# demeter.net
KiCad netlist of a schematic drawn in EAGLE
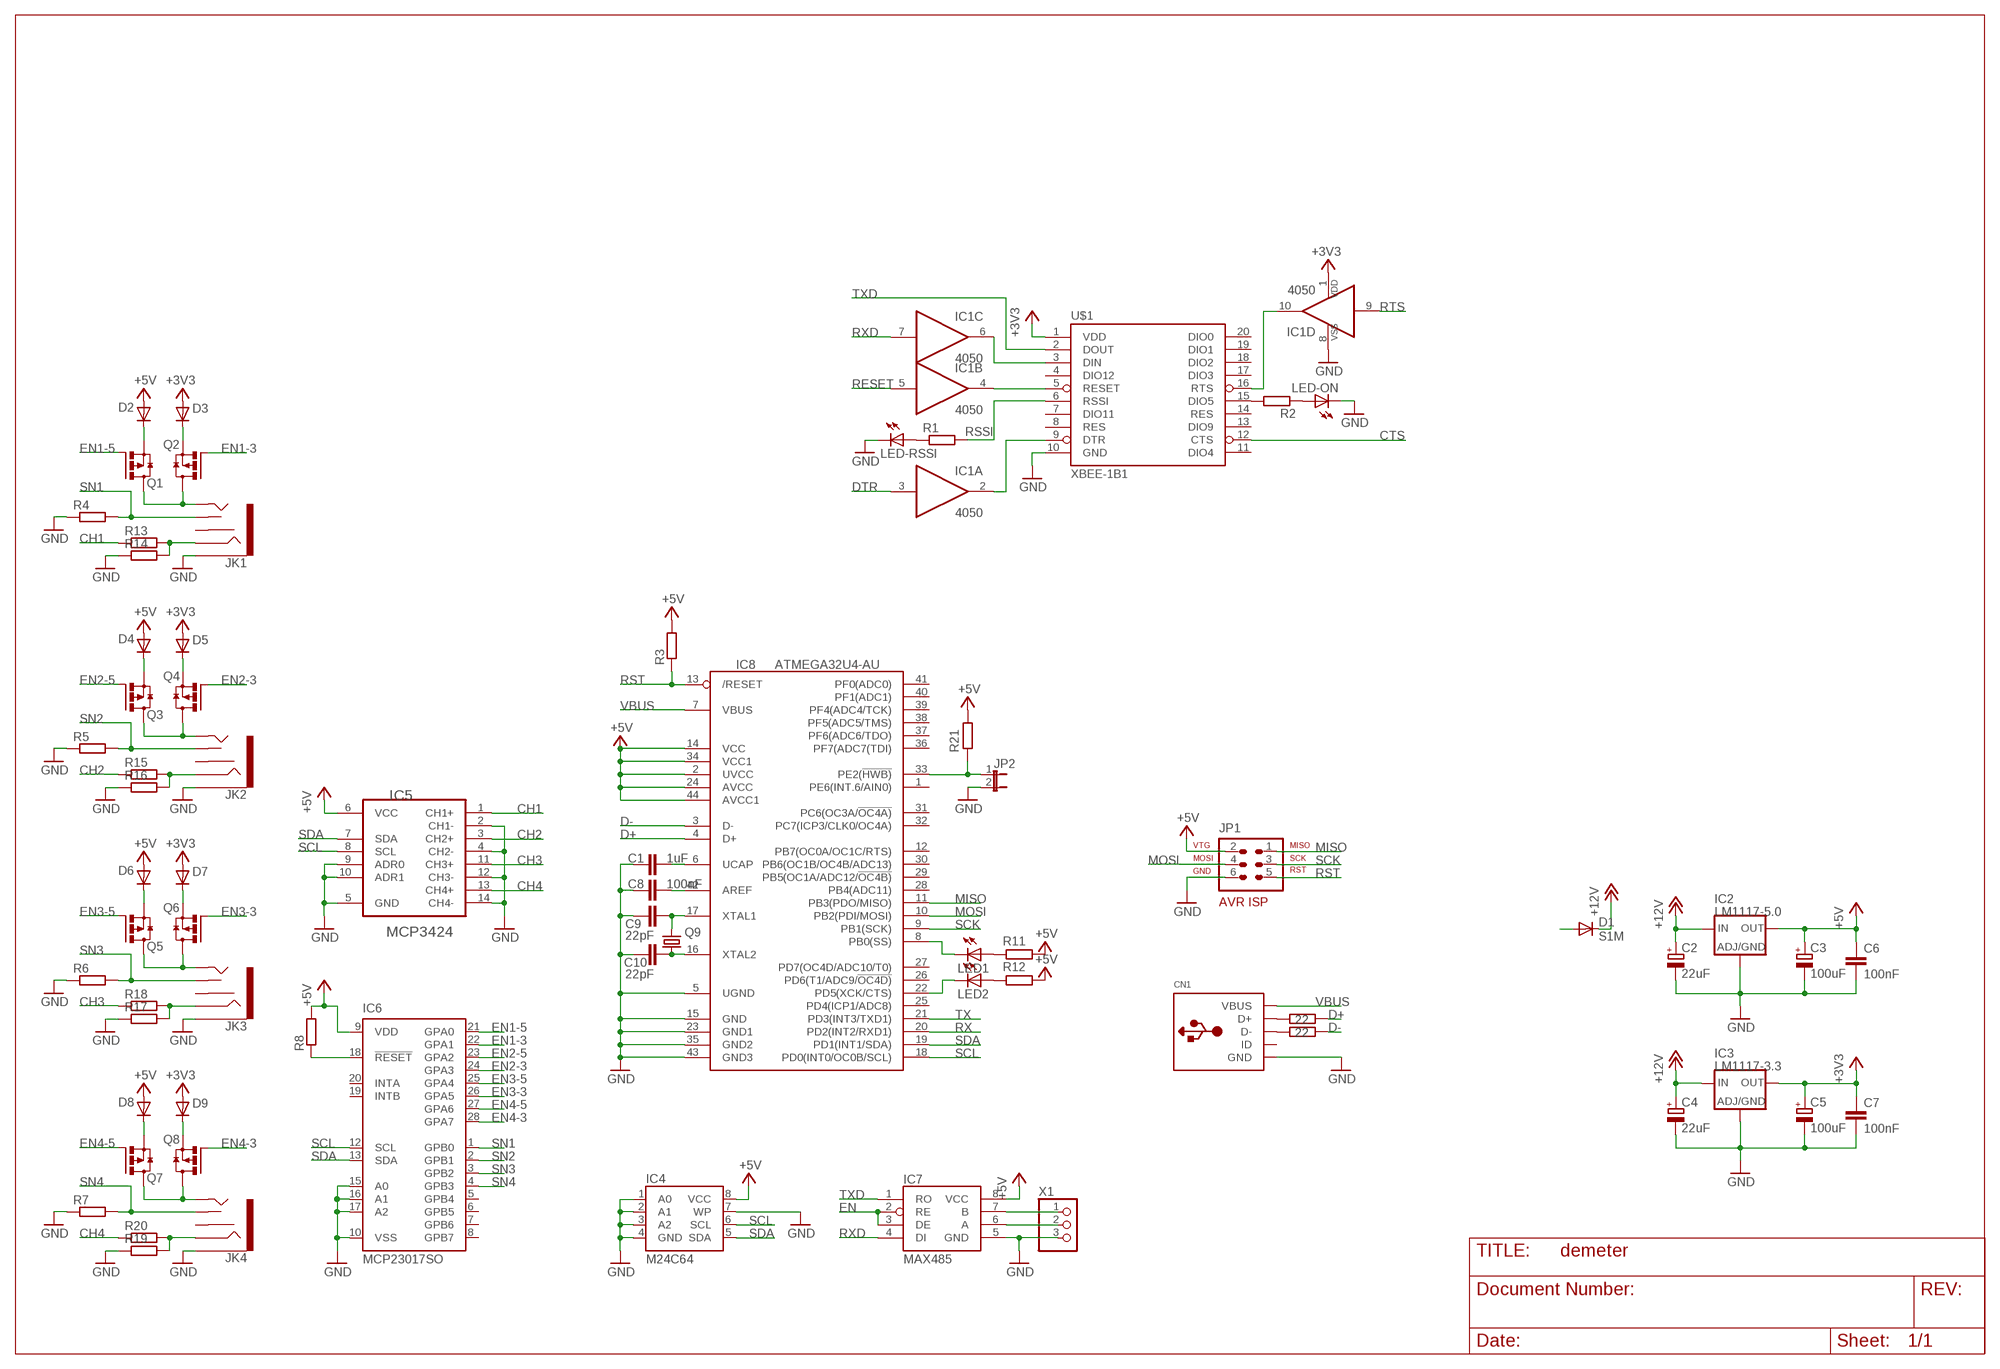
[diagram p0: schematic, sheet 1]

(export (version "E")
  (design (tool "Eeschema 10.0.6"))
  (components
    (comp (ref "C1")
      (value "1uF")
      (footprint "eagle-import:C0805K")
      (libsource (lib "eagle-import") (part "C-EUC0805K"))
    )
    (comp (ref "C2")
      (value "22uF")
      (footprint "eagle-import:PANASONIC_D")
      (libsource (lib "eagle-import") (part "CPOL-EUPD"))
    )
    (comp (ref "C3")
      (value "100uF")
      (footprint "eagle-import:PANASONIC_D")
      (libsource (lib "eagle-import") (part "CPOL-EUPD"))
    )
    (comp (ref "C4")
      (value "22uF")
      (footprint "eagle-import:PANASONIC_D")
      (libsource (lib "eagle-import") (part "CPOL-EUPD"))
    )
    (comp (ref "C5")
      (value "100uF")
      (footprint "eagle-import:PANASONIC_D")
      (libsource (lib "eagle-import") (part "CPOL-EUPD"))
    )
    (comp (ref "C6")
      (value "100nF")
      (footprint "eagle-import:C0805K")
      (libsource (lib "eagle-import") (part "C-EUC0805K"))
    )
    (comp (ref "C7")
      (value "100nF")
      (footprint "eagle-import:C0805K")
      (libsource (lib "eagle-import") (part "C-EUC0805K"))
    )
    (comp (ref "C8")
      (value "100nF")
      (footprint "eagle-import:C0805K")
      (libsource (lib "eagle-import") (part "C-EUC0805K"))
    )
    (comp (ref "C9")
      (value "22pF")
      (footprint "eagle-import:C0805K")
      (libsource (lib "eagle-import") (part "C-EUC0805K"))
    )
    (comp (ref "C10")
      (value "22pF")
      (footprint "eagle-import:C0805K")
      (libsource (lib "eagle-import") (part "C-EUC0805K"))
    )
    (comp (ref "CN1")
      (value "USBMINIB")
      (footprint "eagle-import:USB-MINIB")
      (libsource (lib "eagle-import") (part "USBMINIB"))
    )
    (comp (ref "D1")
      (value "S1M")
      (footprint "eagle-import:DO-214AC")
      (libsource (lib "eagle-import") (part "S1M"))
    )
    (comp (ref "D2")
      (value "MBR0520")
      (footprint "eagle-import:SOD123")
      (libsource (lib "eagle-import") (part "MBR0520"))
    )
    (comp (ref "D3")
      (value "MBR0520")
      (footprint "eagle-import:SOD123")
      (libsource (lib "eagle-import") (part "MBR0520"))
    )
    (comp (ref "D4")
      (value "MBR0520")
      (footprint "eagle-import:SOD123")
      (libsource (lib "eagle-import") (part "MBR0520"))
    )
    (comp (ref "D5")
      (value "MBR0520")
      (footprint "eagle-import:SOD123")
      (libsource (lib "eagle-import") (part "MBR0520"))
    )
    (comp (ref "D6")
      (value "MBR0520")
      (footprint "eagle-import:SOD123")
      (libsource (lib "eagle-import") (part "MBR0520"))
    )
    (comp (ref "D7")
      (value "MBR0520")
      (footprint "eagle-import:SOD123")
      (libsource (lib "eagle-import") (part "MBR0520"))
    )
    (comp (ref "D8")
      (value "MBR0520")
      (footprint "eagle-import:SOD123")
      (libsource (lib "eagle-import") (part "MBR0520"))
    )
    (comp (ref "D9")
      (value "MBR0520")
      (footprint "eagle-import:SOD123")
      (libsource (lib "eagle-import") (part "MBR0520"))
    )
    (comp (ref "IC1")
      (value "4050")
      (footprint "eagle-import:SO16")
      (libsource (lib "eagle-import") (part "4050D"))
    )
    (comp (ref "IC2")
      (value "LM1117-5.0")
      (footprint "eagle-import:DPACK")
      (libsource (lib "eagle-import") (part "LM1117DT"))
    )
    (comp (ref "IC3")
      (value "LM1117-3.3")
      (footprint "eagle-import:DPACK")
      (libsource (lib "eagle-import") (part "LM1117DT"))
    )
    (comp (ref "IC4")
      (value "M24C64")
      (footprint "eagle-import:SO08")
      (libsource (lib "eagle-import") (part "AT24C"))
    )
    (comp (ref "IC5")
      (value "MCP3424")
      (footprint "eagle-import:SO14")
      (fields (field (name "MPN") "MCP3424-E/SL"))
      (libsource (lib "eagle-import") (part "MCP3424"))
    )
    (comp (ref "IC6")
      (value "MCP23017SO")
      (footprint "eagle-import:SO28W")
      (fields (field (name "MF") "MICROCHIP") (field (name "MPN") "MCP23017-E/SO"))
      (libsource (lib "eagle-import") (part "MCP23017SO"))
    )
    (comp (ref "IC7")
      (value "MAX485")
      (footprint "eagle-import:SO08")
      (libsource (lib "eagle-import") (part "MAX485"))
    )
    (comp (ref "IC8")
      (value "ATMEGA32U4-AU")
      (footprint "eagle-import:TQFP44")
      (libsource (lib "eagle-import") (part "ATMEGA32U4-AU"))
    )
    (comp (ref "JK1")
      (value "AUDIO-JACK2PTH")
      (footprint "eagle-import:AUDIO-JACK")
      (libsource (lib "eagle-import") (part "AUDIO-JACK2PTH"))
    )
    (comp (ref "JK2")
      (value "AUDIO-JACK2PTH")
      (footprint "eagle-import:AUDIO-JACK")
      (libsource (lib "eagle-import") (part "AUDIO-JACK2PTH"))
    )
    (comp (ref "JK3")
      (value "AUDIO-JACK2PTH")
      (footprint "eagle-import:AUDIO-JACK")
      (libsource (lib "eagle-import") (part "AUDIO-JACK2PTH"))
    )
    (comp (ref "JK4")
      (value "AUDIO-JACK2PTH")
      (footprint "eagle-import:AUDIO-JACK")
      (libsource (lib "eagle-import") (part "AUDIO-JACK2PTH"))
    )
    (comp (ref "JP1")
      (value "AVR-ISP-6")
      (footprint "eagle-import:AVR-ISP-6")
      (libsource (lib "eagle-import") (part "AVR-ISP-6"))
    )
    (comp (ref "JP2")
      (value "JUMPER-2SMD-NO")
      (footprint "eagle-import:SJ_2S-NO")
      (libsource (lib "eagle-import") (part "JUMPER-2SMD-NO"))
    )
    (comp (ref "LED-ON")
      (value "LED3MM")
      (footprint "eagle-import:LED3MM")
      (libsource (lib "eagle-import") (part "LED3MM"))
    )
    (comp (ref "LED-RSSI")
      (value "LED3MM")
      (footprint "eagle-import:LED3MM")
      (libsource (lib "eagle-import") (part "LED3MM"))
    )
    (comp (ref "LED1")
      (value "LED0805")
      (footprint "eagle-import:CHIP-LED0805")
      (libsource (lib "eagle-import") (part "mark_2_LED0805"))
    )
    (comp (ref "LED2")
      (value "LED0805")
      (footprint "eagle-import:CHIP-LED0805")
      (libsource (lib "eagle-import") (part "mark_2_LED0805"))
    )
    (comp (ref "Q1")
      (value "IRLML6402")
      (footprint "eagle-import:SOT23")
      (libsource (lib "eagle-import") (part "IRLML6402"))
    )
    (comp (ref "Q2")
      (value "IRLML6402")
      (footprint "eagle-import:SOT23")
      (libsource (lib "eagle-import") (part "IRLML6402"))
    )
    (comp (ref "Q3")
      (value "IRLML6402")
      (footprint "eagle-import:SOT23")
      (libsource (lib "eagle-import") (part "IRLML6402"))
    )
    (comp (ref "Q4")
      (value "IRLML6402")
      (footprint "eagle-import:SOT23")
      (libsource (lib "eagle-import") (part "IRLML6402"))
    )
    (comp (ref "Q5")
      (value "IRLML6402")
      (footprint "eagle-import:SOT23")
      (libsource (lib "eagle-import") (part "IRLML6402"))
    )
    (comp (ref "Q6")
      (value "IRLML6402")
      (footprint "eagle-import:SOT23")
      (libsource (lib "eagle-import") (part "IRLML6402"))
    )
    (comp (ref "Q7")
      (value "IRLML6402")
      (footprint "eagle-import:SOT23")
      (libsource (lib "eagle-import") (part "IRLML6402"))
    )
    (comp (ref "Q8")
      (value "IRLML6402")
      (footprint "eagle-import:SOT23")
      (libsource (lib "eagle-import") (part "IRLML6402"))
    )
    (comp (ref "Q9")
      (value "CRYSTALHC49UP")
      (footprint "eagle-import:HC49UP")
      (libsource (lib "eagle-import") (part "CRYSTALHC49UP"))
    )
    (comp (ref "R1")
      (value "R-EU_R0805")
      (footprint "eagle-import:R0805")
      (libsource (lib "eagle-import") (part "R-EU_R0805"))
    )
    (comp (ref "R2")
      (value "R-EU_R0805")
      (footprint "eagle-import:R0805")
      (libsource (lib "eagle-import") (part "R-EU_R0805"))
    )
    (comp (ref "R3")
      (value "R-EU_R0805")
      (footprint "eagle-import:R0805")
      (libsource (lib "eagle-import") (part "R-EU_R0805"))
    )
    (comp (ref "R4")
      (value "R-EU_R0805")
      (footprint "eagle-import:R0805")
      (libsource (lib "eagle-import") (part "R-EU_R0805"))
    )
    (comp (ref "R5")
      (value "R-EU_R0805")
      (footprint "eagle-import:R0805")
      (libsource (lib "eagle-import") (part "R-EU_R0805"))
    )
    (comp (ref "R6")
      (value "R-EU_R0805")
      (footprint "eagle-import:R0805")
      (libsource (lib "eagle-import") (part "R-EU_R0805"))
    )
    (comp (ref "R7")
      (value "R-EU_R0805")
      (footprint "eagle-import:R0805")
      (libsource (lib "eagle-import") (part "R-EU_R0805"))
    )
    (comp (ref "R8")
      (value "R-EU_R0805")
      (footprint "eagle-import:R0805")
      (libsource (lib "eagle-import") (part "R-EU_R0805"))
    )
    (comp (ref "R9")
      (value "22")
      (footprint "eagle-import:R0805")
      (libsource (lib "eagle-import") (part "R-EU_R0805"))
    )
    (comp (ref "R10")
      (value "22")
      (footprint "eagle-import:R0805")
      (libsource (lib "eagle-import") (part "R-EU_R0805"))
    )
    (comp (ref "R11")
      (value "R-EU_R0805")
      (footprint "eagle-import:R0805")
      (libsource (lib "eagle-import") (part "R-EU_R0805"))
    )
    (comp (ref "R12")
      (value "R-EU_R0805")
      (footprint "eagle-import:R0805")
      (libsource (lib "eagle-import") (part "R-EU_R0805"))
    )
    (comp (ref "R13")
      (value "R-EU_R0805")
      (footprint "eagle-import:R0805")
      (libsource (lib "eagle-import") (part "R-EU_R0805"))
    )
    (comp (ref "R14")
      (value "R-EU_R0805")
      (footprint "eagle-import:R0805")
      (libsource (lib "eagle-import") (part "R-EU_R0805"))
    )
    (comp (ref "R15")
      (value "R-EU_R0805")
      (footprint "eagle-import:R0805")
      (libsource (lib "eagle-import") (part "R-EU_R0805"))
    )
    (comp (ref "R16")
      (value "R-EU_R0805")
      (footprint "eagle-import:R0805")
      (libsource (lib "eagle-import") (part "R-EU_R0805"))
    )
    (comp (ref "R17")
      (value "R-EU_R0805")
      (footprint "eagle-import:R0805")
      (libsource (lib "eagle-import") (part "R-EU_R0805"))
    )
    (comp (ref "R18")
      (value "R-EU_R0805")
      (footprint "eagle-import:R0805")
      (libsource (lib "eagle-import") (part "R-EU_R0805"))
    )
    (comp (ref "R19")
      (value "R-EU_R0805")
      (footprint "eagle-import:R0805")
      (libsource (lib "eagle-import") (part "R-EU_R0805"))
    )
    (comp (ref "R20")
      (value "R-EU_R0805")
      (footprint "eagle-import:R0805")
      (libsource (lib "eagle-import") (part "R-EU_R0805"))
    )
    (comp (ref "R21")
      (value "R-EU_R0805")
      (footprint "eagle-import:R0805")
      (libsource (lib "eagle-import") (part "R-EU_R0805"))
    )
    (comp (ref "U$1")
      (value "XBEE-1B1")
      (footprint "eagle-import:XBEE-1")
      (libsource (lib "eagle-import") (part "XBEE-1B1"))
    )
    (comp (ref "X1")
      (value "W237-103")
      (footprint "eagle-import:W237-103")
      (libsource (lib "eagle-import") (part "W237-103"))
    )
  )
  (nets
    (net (code "1") (name "+3V3") (class "Default")
      (node (ref "C5") (pin "+") (pinfunction "+_+") (pintype "passive"))
      (node (ref "C7") (pin "1") (pinfunction "1_1") (pintype "passive"))
      (node (ref "D3") (pin "A") (pinfunction "A_A") (pintype "passive"))
      (node (ref "D5") (pin "A") (pinfunction "A_A") (pintype "passive"))
      (node (ref "D7") (pin "A") (pinfunction "A_A") (pintype "passive"))
      (node (ref "D9") (pin "A") (pinfunction "A_A") (pintype "passive"))
      (node (ref "IC1") (pin "1") (pinfunction "VDD_1") (pintype "power_in"))
      (node (ref "IC3") (pin "4") (pinfunction "OUT_4") (pintype "passive"))
      (node (ref "U$1") (pin "1") (pinfunction "VDD_1") (pintype "power_in"))
    )
    (net (code "2") (name "+5V") (class "Default")
      (node (ref "C3") (pin "+") (pinfunction "+_+") (pintype "passive"))
      (node (ref "C6") (pin "1") (pinfunction "1_1") (pintype "passive"))
      (node (ref "D2") (pin "A") (pinfunction "A_A") (pintype "passive"))
      (node (ref "D4") (pin "A") (pinfunction "A_A") (pintype "passive"))
      (node (ref "D6") (pin "A") (pinfunction "A_A") (pintype "passive"))
      (node (ref "D8") (pin "A") (pinfunction "A_A") (pintype "passive"))
      (node (ref "IC2") (pin "4") (pinfunction "OUT_4") (pintype "passive"))
      (node (ref "IC4") (pin "8") (pinfunction "VCC_8") (pintype "power_in"))
      (node (ref "IC5") (pin "6") (pinfunction "VCC_6") (pintype "power_in"))
      (node (ref "IC6") (pin "9") (pinfunction "VDD_9") (pintype "power_in"))
      (node (ref "IC7") (pin "8") (pinfunction "VCC_8") (pintype "bidirectional"))
      (node (ref "IC8") (pin "14") (pinfunction "VCC_14") (pintype "bidirectional"))
      (node (ref "IC8") (pin "2") (pinfunction "UVCC_2") (pintype "bidirectional"))
      (node (ref "IC8") (pin "24") (pinfunction "AVCC_24") (pintype "bidirectional"))
      (node (ref "IC8") (pin "34") (pinfunction "VCC1_34") (pintype "bidirectional"))
      (node (ref "IC8") (pin "44") (pinfunction "AVCC1_44") (pintype "bidirectional"))
      (node (ref "JP1") (pin "2") (pinfunction "VTG_2") (pintype "passive"))
      (node (ref "R11") (pin "1") (pinfunction "1_1") (pintype "passive"))
      (node (ref "R12") (pin "1") (pinfunction "1_1") (pintype "passive"))
      (node (ref "R21") (pin "1") (pinfunction "1_1") (pintype "passive"))
      (node (ref "R3") (pin "2") (pinfunction "2_2") (pintype "passive"))
      (node (ref "R8") (pin "2") (pinfunction "2_2") (pintype "passive"))
    )
    (net (code "3") (name "+12V") (class "Default")
      (node (ref "C2") (pin "+") (pinfunction "+_+") (pintype "passive"))
      (node (ref "C4") (pin "+") (pinfunction "+_+") (pintype "passive"))
      (node (ref "D1") (pin "C") (pinfunction "C_C") (pintype "passive"))
      (node (ref "IC2") (pin "3") (pinfunction "IN_3") (pintype "input"))
      (node (ref "IC3") (pin "3") (pinfunction "IN_3") (pintype "input"))
    )
    (net (code "4") (name "/CH1") (class "Default")
      (node (ref "IC5") (pin "1") (pinfunction "CH1+_1") (pintype "input"))
      (node (ref "R13") (pin "1") (pinfunction "1_1") (pintype "passive"))
    )
    (net (code "5") (name "/CH2") (class "Default")
      (node (ref "IC5") (pin "3") (pinfunction "CH2+_3") (pintype "input"))
      (node (ref "R15") (pin "1") (pinfunction "1_1") (pintype "passive"))
    )
    (net (code "6") (name "/CH3") (class "Default")
      (node (ref "IC5") (pin "11") (pinfunction "CH3+_11") (pintype "input"))
      (node (ref "R18") (pin "1") (pinfunction "1_1") (pintype "passive"))
    )
    (net (code "7") (name "/CH4") (class "Default")
      (node (ref "IC5") (pin "13") (pinfunction "CH4+_13") (pintype "input"))
      (node (ref "R20") (pin "1") (pinfunction "1_1") (pintype "passive"))
    )
    (net (code "8") (name "/CTS") (class "Default")
      (node (ref "U$1") (pin "12") (pinfunction "CTS_12") (pintype "output"))
    )
    (net (code "9") (name "/D+") (class "Default")
      (node (ref "IC8") (pin "4") (pinfunction "D+_4") (pintype "bidirectional"))
      (node (ref "R9") (pin "1") (pinfunction "1_1") (pintype "passive"))
    )
    (net (code "10") (name "/D-") (class "Default")
      (node (ref "IC8") (pin "3") (pinfunction "D-_3") (pintype "bidirectional"))
      (node (ref "R10") (pin "1") (pinfunction "1_1") (pintype "passive"))
    )
    (net (code "11") (name "/DTR") (class "Default")
      (node (ref "IC1") (pin "3") (pinfunction "I_3") (pintype "input"))
    )
    (net (code "12") (name "/EN") (class "Default")
      (node (ref "IC7") (pin "2") (pinfunction "RE_2") (pintype "bidirectional"))
      (node (ref "IC7") (pin "3") (pinfunction "DE_3") (pintype "bidirectional"))
    )
    (net (code "13") (name "/EN1-3") (class "Default")
      (node (ref "IC6") (pin "22") (pinfunction "GPA1_22") (pintype "bidirectional"))
      (node (ref "Q2") (pin "1") (pinfunction "G_1") (pintype "passive"))
    )
    (net (code "14") (name "/EN1-5") (class "Default")
      (node (ref "IC6") (pin "21") (pinfunction "GPA0_21") (pintype "bidirectional"))
      (node (ref "Q1") (pin "1") (pinfunction "G_1") (pintype "passive"))
    )
    (net (code "15") (name "/EN2-3") (class "Default")
      (node (ref "IC6") (pin "24") (pinfunction "GPA3_24") (pintype "bidirectional"))
      (node (ref "Q4") (pin "1") (pinfunction "G_1") (pintype "passive"))
    )
    (net (code "16") (name "/EN2-5") (class "Default")
      (node (ref "IC6") (pin "23") (pinfunction "GPA2_23") (pintype "bidirectional"))
      (node (ref "Q3") (pin "1") (pinfunction "G_1") (pintype "passive"))
    )
    (net (code "17") (name "/EN3-3") (class "Default")
      (node (ref "IC6") (pin "26") (pinfunction "GPA5_26") (pintype "bidirectional"))
      (node (ref "Q6") (pin "1") (pinfunction "G_1") (pintype "passive"))
    )
    (net (code "18") (name "/EN3-5") (class "Default")
      (node (ref "IC6") (pin "25") (pinfunction "GPA4_25") (pintype "bidirectional"))
      (node (ref "Q5") (pin "1") (pinfunction "G_1") (pintype "passive"))
    )
    (net (code "19") (name "/EN4-3") (class "Default")
      (node (ref "IC6") (pin "28") (pinfunction "GPA7_28") (pintype "bidirectional"))
      (node (ref "Q8") (pin "1") (pinfunction "G_1") (pintype "passive"))
    )
    (net (code "20") (name "/EN4-5") (class "Default")
      (node (ref "IC6") (pin "27") (pinfunction "GPA6_27") (pintype "bidirectional"))
      (node (ref "Q7") (pin "1") (pinfunction "G_1") (pintype "passive"))
    )
    (net (code "21") (name "/MISO") (class "Default")
      (node (ref "IC8") (pin "11") (pinfunction "PB3(PDO/MISO)_11") (pintype "bidirectional"))
      (node (ref "JP1") (pin "1") (pinfunction "MISO_1") (pintype "passive"))
    )
    (net (code "22") (name "/MOSI") (class "Default")
      (node (ref "IC8") (pin "10") (pinfunction "PB2(PDI/MOSI)_10") (pintype "bidirectional"))
      (node (ref "JP1") (pin "4") (pinfunction "MOSI_4") (pintype "passive"))
    )
    (net (code "23") (name "/RESET") (class "Default")
      (node (ref "IC1") (pin "5") (pinfunction "I_5") (pintype "input"))
    )
    (net (code "24") (name "/RSSI") (class "Default")
      (node (ref "R1") (pin "2") (pinfunction "2_2") (pintype "passive"))
      (node (ref "U$1") (pin "6") (pinfunction "RSSI_6") (pintype "bidirectional"))
    )
    (net (code "25") (name "/RST") (class "Default")
      (node (ref "IC8") (pin "13") (pinfunction "/RESET_13") (pintype "bidirectional"))
      (node (ref "JP1") (pin "5") (pinfunction "RST_5") (pintype "passive"))
      (node (ref "R3") (pin "1") (pinfunction "1_1") (pintype "passive"))
    )
    (net (code "26") (name "/RTS") (class "Default")
      (node (ref "IC1") (pin "9") (pinfunction "I_9") (pintype "input"))
    )
    (net (code "27") (name "/RX") (class "Default")
      (node (ref "IC8") (pin "20") (pinfunction "PD2(INT2/RXD1)_20") (pintype "bidirectional"))
    )
    (net (code "28") (name "/RXD") (class "Default")
      (node (ref "IC1") (pin "7") (pinfunction "I_7") (pintype "input"))
      (node (ref "IC7") (pin "4") (pinfunction "DI_4") (pintype "bidirectional"))
    )
    (net (code "29") (name "/SCK") (class "Default")
      (node (ref "IC8") (pin "9") (pinfunction "PB1(SCK)_9") (pintype "bidirectional"))
      (node (ref "JP1") (pin "3") (pinfunction "SCK_3") (pintype "passive"))
    )
    (net (code "30") (name "/SCL") (class "Default")
      (node (ref "IC4") (pin "6") (pinfunction "SCL_6") (pintype "bidirectional"))
      (node (ref "IC5") (pin "8") (pinfunction "SCL_8") (pintype "input"))
      (node (ref "IC6") (pin "12") (pinfunction "SCL_12") (pintype "input"))
      (node (ref "IC8") (pin "18") (pinfunction "PD0(INT0/OC0B/SCL)_18") (pintype "bidirectional"))
    )
    (net (code "31") (name "/SDA") (class "Default")
      (node (ref "IC4") (pin "5") (pinfunction "SDA_5") (pintype "bidirectional"))
      (node (ref "IC5") (pin "7") (pinfunction "SDA_7") (pintype "bidirectional"))
      (node (ref "IC6") (pin "13") (pinfunction "SDA_13") (pintype "bidirectional"))
      (node (ref "IC8") (pin "19") (pinfunction "PD1(INT1/SDA)_19") (pintype "bidirectional"))
    )
    (net (code "32") (name "/SN1") (class "Default")
      (node (ref "IC6") (pin "1") (pinfunction "GPB0_1") (pintype "bidirectional"))
      (node (ref "JK1") (pin "TSH") (pinfunction "TSH_TSH") (pintype "bidirectional"))
      (node (ref "R4") (pin "2") (pinfunction "2_2") (pintype "passive"))
    )
    (net (code "33") (name "/SN2") (class "Default")
      (node (ref "IC6") (pin "2") (pinfunction "GPB1_2") (pintype "bidirectional"))
      (node (ref "JK2") (pin "TSH") (pinfunction "TSH_TSH") (pintype "bidirectional"))
      (node (ref "R5") (pin "2") (pinfunction "2_2") (pintype "passive"))
    )
    (net (code "34") (name "/SN3") (class "Default")
      (node (ref "IC6") (pin "3") (pinfunction "GPB2_3") (pintype "bidirectional"))
      (node (ref "JK3") (pin "TSH") (pinfunction "TSH_TSH") (pintype "bidirectional"))
      (node (ref "R6") (pin "2") (pinfunction "2_2") (pintype "passive"))
    )
    (net (code "35") (name "/SN4") (class "Default")
      (node (ref "IC6") (pin "4") (pinfunction "GPB3_4") (pintype "bidirectional"))
      (node (ref "JK4") (pin "TSH") (pinfunction "TSH_TSH") (pintype "bidirectional"))
      (node (ref "R7") (pin "2") (pinfunction "2_2") (pintype "passive"))
    )
    (net (code "36") (name "/TX") (class "Default")
      (node (ref "IC8") (pin "21") (pinfunction "PD3(INT3/TXD1)_21") (pintype "bidirectional"))
    )
    (net (code "37") (name "/TXD") (class "Default")
      (node (ref "IC7") (pin "1") (pinfunction "RO_1") (pintype "bidirectional"))
      (node (ref "U$1") (pin "2") (pinfunction "DOUT_2") (pintype "output"))
    )
    (net (code "38") (name "/VBUS") (class "Default")
      (node (ref "CN1") (pin "VBUS") (pinfunction "VBUS_VBUS") (pintype "power_in"))
      (node (ref "IC8") (pin "7") (pinfunction "VBUS_7") (pintype "bidirectional"))
    )
    (net (code "39") (name "GND") (class "Default")
      (node (ref "C1") (pin "2") (pinfunction "2_2") (pintype "passive"))
      (node (ref "C10") (pin "2") (pinfunction "2_2") (pintype "passive"))
      (node (ref "C2") (pin "-") (pinfunction "-_-") (pintype "passive"))
      (node (ref "C3") (pin "-") (pinfunction "-_-") (pintype "passive"))
      (node (ref "C4") (pin "-") (pinfunction "-_-") (pintype "passive"))
      (node (ref "C5") (pin "-") (pinfunction "-_-") (pintype "passive"))
      (node (ref "C6") (pin "2") (pinfunction "2_2") (pintype "passive"))
      (node (ref "C7") (pin "2") (pinfunction "2_2") (pintype "passive"))
      (node (ref "C8") (pin "2") (pinfunction "2_2") (pintype "passive"))
      (node (ref "C9") (pin "2") (pinfunction "2_2") (pintype "passive"))
      (node (ref "CN1") (pin "GND") (pinfunction "GND_GND") (pintype "power_in"))
      (node (ref "IC1") (pin "8") (pinfunction "VSS_8") (pintype "power_in"))
      (node (ref "IC2") (pin "1") (pinfunction "ADJ_1") (pintype "input"))
      (node (ref "IC3") (pin "1") (pinfunction "ADJ_1") (pintype "input"))
      (node (ref "IC4") (pin "1") (pinfunction "A0_1") (pintype "input"))
      (node (ref "IC4") (pin "2") (pinfunction "A1_2") (pintype "input"))
      (node (ref "IC4") (pin "3") (pinfunction "A2_3") (pintype "input"))
      (node (ref "IC4") (pin "4") (pinfunction "GND_4") (pintype "power_in"))
      (node (ref "IC4") (pin "7") (pinfunction "WP_7") (pintype "input"))
      (node (ref "IC5") (pin "10") (pinfunction "ADR1_10") (pintype "input"))
      (node (ref "IC5") (pin "12") (pinfunction "CH3-_12") (pintype "input"))
      (node (ref "IC5") (pin "14") (pinfunction "CH4-_14") (pintype "input"))
      (node (ref "IC5") (pin "2") (pinfunction "CH1-_2") (pintype "input"))
      (node (ref "IC5") (pin "4") (pinfunction "CH2-_4") (pintype "input"))
      (node (ref "IC5") (pin "5") (pinfunction "GND_5") (pintype "power_in"))
      (node (ref "IC5") (pin "9") (pinfunction "ADR0_9") (pintype "input"))
      (node (ref "IC6") (pin "10") (pinfunction "VSS_10") (pintype "power_in"))
      (node (ref "IC6") (pin "15") (pinfunction "A0_15") (pintype "input"))
      (node (ref "IC6") (pin "16") (pinfunction "A1_16") (pintype "input"))
      (node (ref "IC6") (pin "17") (pinfunction "A2_17") (pintype "input"))
      (node (ref "IC7") (pin "5") (pinfunction "GND_5") (pintype "bidirectional"))
      (node (ref "IC8") (pin "15") (pinfunction "GND_15") (pintype "bidirectional"))
      (node (ref "IC8") (pin "23") (pinfunction "GND1_23") (pintype "bidirectional"))
      (node (ref "IC8") (pin "35") (pinfunction "GND2_35") (pintype "bidirectional"))
      (node (ref "IC8") (pin "43") (pinfunction "GND3_43") (pintype "bidirectional"))
      (node (ref "IC8") (pin "5") (pinfunction "UGND_5") (pintype "bidirectional"))
      (node (ref "JK1") (pin "SLEEVE") (pinfunction "SLEEVE_SLEEVE") (pintype "bidirectional"))
      (node (ref "JK2") (pin "SLEEVE") (pinfunction "SLEEVE_SLEEVE") (pintype "bidirectional"))
      (node (ref "JK3") (pin "SLEEVE") (pinfunction "SLEEVE_SLEEVE") (pintype "bidirectional"))
      (node (ref "JK4") (pin "SLEEVE") (pinfunction "SLEEVE_SLEEVE") (pintype "bidirectional"))
      (node (ref "JP1") (pin "6") (pinfunction "GND_6") (pintype "passive"))
      (node (ref "JP2") (pin "2") (pinfunction "2_2") (pintype "passive"))
      (node (ref "LED-ON") (pin "K") (pinfunction "C_K") (pintype "passive"))
      (node (ref "LED-RSSI") (pin "K") (pinfunction "C_K") (pintype "passive"))
      (node (ref "R14") (pin "1") (pinfunction "1_1") (pintype "passive"))
      (node (ref "R16") (pin "1") (pinfunction "1_1") (pintype "passive"))
      (node (ref "R17") (pin "1") (pinfunction "1_1") (pintype "passive"))
      (node (ref "R19") (pin "1") (pinfunction "1_1") (pintype "passive"))
      (node (ref "R4") (pin "1") (pinfunction "1_1") (pintype "passive"))
      (node (ref "R5") (pin "1") (pinfunction "1_1") (pintype "passive"))
      (node (ref "R6") (pin "1") (pinfunction "1_1") (pintype "passive"))
      (node (ref "R7") (pin "1") (pinfunction "1_1") (pintype "passive"))
      (node (ref "U$1") (pin "10") (pinfunction "GND_10") (pintype "power_in"))
      (node (ref "X1") (pin "3") (pinfunction "3_3") (pintype "passive"))
    )
    (net (code "40") (name "Net-(CN1-PadD+)") (class "Default")
      (node (ref "CN1") (pin "D+") (pinfunction "D+_D+") (pintype "bidirectional"))
      (node (ref "R9") (pin "2") (pinfunction "2_2") (pintype "passive"))
    )
    (net (code "41") (name "Net-(CN1-PadD-)") (class "Default")
      (node (ref "CN1") (pin "D-") (pinfunction "D-_D-") (pintype "bidirectional"))
      (node (ref "R10") (pin "2") (pinfunction "2_2") (pintype "passive"))
    )
    (net (code "42") (name "Net-(IC1A-O)") (class "Default")
      (node (ref "IC1") (pin "2") (pinfunction "O_2") (pintype "output"))
      (node (ref "U$1") (pin "9") (pinfunction "DTR_9") (pintype "bidirectional"))
    )
    (net (code "43") (name "Net-(IC1B-O)") (class "Default")
      (node (ref "IC1") (pin "4") (pinfunction "O_4") (pintype "output"))
      (node (ref "U$1") (pin "5") (pinfunction "RESET_5") (pintype "input"))
    )
    (net (code "44") (name "Net-(IC1C-O)") (class "Default")
      (node (ref "IC1") (pin "6") (pinfunction "O_6") (pintype "output"))
      (node (ref "U$1") (pin "3") (pinfunction "DIN_3") (pintype "input"))
    )
    (net (code "45") (name "Net-(IC1D-O)") (class "Default")
      (node (ref "IC1") (pin "10") (pinfunction "O_10") (pintype "output"))
      (node (ref "U$1") (pin "16") (pinfunction "RTS_16") (pintype "input"))
    )
    (net (code "46") (name "Net-(IC6-~{RESET})") (class "Default")
      (node (ref "IC6") (pin "18") (pinfunction "~{RESET}_18") (pintype "input"))
      (node (ref "R8") (pin "1") (pinfunction "1_1") (pintype "passive"))
    )
    (net (code "47") (name "Net-(IC7-A)") (class "Default")
      (node (ref "IC7") (pin "6") (pinfunction "A_6") (pintype "bidirectional"))
      (node (ref "X1") (pin "2") (pinfunction "2_2") (pintype "passive"))
    )
    (net (code "48") (name "Net-(IC7-B)") (class "Default")
      (node (ref "IC7") (pin "7") (pinfunction "B_7") (pintype "bidirectional"))
      (node (ref "X1") (pin "1") (pinfunction "1_1") (pintype "passive"))
    )
    (net (code "49") (name "Net-(IC8-AREF)") (class "Default")
      (node (ref "C8") (pin "1") (pinfunction "1_1") (pintype "passive"))
      (node (ref "IC8") (pin "42") (pinfunction "AREF_42") (pintype "bidirectional"))
    )
    (net (code "50") (name "Net-(IC8-PB0(SS))") (class "Default")
      (node (ref "IC8") (pin "8") (pinfunction "PB0(SS)_8") (pintype "bidirectional"))
      (node (ref "LED1") (pin "C") (pinfunction "C_C") (pintype "passive"))
    )
    (net (code "51") (name "Net-(IC8-PD5(XCK{slash}CTS))") (class "Default")
      (node (ref "IC8") (pin "22") (pinfunction "PD5(XCK/CTS)_22") (pintype "bidirectional"))
      (node (ref "LED2") (pin "C") (pinfunction "C_C") (pintype "passive"))
    )
    (net (code "52") (name "Net-(IC8-PE2(~{HWB}))") (class "Default")
      (node (ref "IC8") (pin "33") (pinfunction "PE2(~{HWB})_33") (pintype "bidirectional"))
      (node (ref "JP2") (pin "1") (pinfunction "1_1") (pintype "passive"))
      (node (ref "R21") (pin "2") (pinfunction "2_2") (pintype "passive"))
    )
    (net (code "53") (name "Net-(IC8-UCAP)") (class "Default")
      (node (ref "C1") (pin "1") (pinfunction "1_1") (pintype "passive"))
      (node (ref "IC8") (pin "6") (pinfunction "UCAP_6") (pintype "bidirectional"))
    )
    (net (code "54") (name "Net-(IC8-XTAL1)") (class "Default")
      (node (ref "C9") (pin "1") (pinfunction "1_1") (pintype "passive"))
      (node (ref "IC8") (pin "17") (pinfunction "XTAL1_17") (pintype "bidirectional"))
      (node (ref "Q9") (pin "2") (pinfunction "2_2") (pintype "passive"))
    )
    (net (code "55") (name "Net-(IC8-XTAL2)") (class "Default")
      (node (ref "C10") (pin "1") (pinfunction "1_1") (pintype "passive"))
      (node (ref "IC8") (pin "16") (pinfunction "XTAL2_16") (pintype "bidirectional"))
      (node (ref "Q9") (pin "1") (pinfunction "1_1") (pintype "passive"))
    )
    (net (code "56") (name "Net-(JK1-PadRING)") (class "Default")
      (node (ref "JK1") (pin "RING") (pinfunction "RING_RING") (pintype "bidirectional"))
      (node (ref "R13") (pin "2") (pinfunction "2_2") (pintype "passive"))
      (node (ref "R14") (pin "2") (pinfunction "2_2") (pintype "passive"))
    )
    (net (code "57") (name "Net-(JK2-PadRING)") (class "Default")
      (node (ref "JK2") (pin "RING") (pinfunction "RING_RING") (pintype "bidirectional"))
      (node (ref "R15") (pin "2") (pinfunction "2_2") (pintype "passive"))
      (node (ref "R16") (pin "2") (pinfunction "2_2") (pintype "passive"))
    )
    (net (code "58") (name "Net-(JK3-PadRING)") (class "Default")
      (node (ref "JK3") (pin "RING") (pinfunction "RING_RING") (pintype "bidirectional"))
      (node (ref "R17") (pin "2") (pinfunction "2_2") (pintype "passive"))
      (node (ref "R18") (pin "2") (pinfunction "2_2") (pintype "passive"))
    )
    (net (code "59") (name "Net-(JK4-PadRING)") (class "Default")
      (node (ref "JK4") (pin "RING") (pinfunction "RING_RING") (pintype "bidirectional"))
      (node (ref "R19") (pin "2") (pinfunction "2_2") (pintype "passive"))
      (node (ref "R20") (pin "2") (pinfunction "2_2") (pintype "passive"))
    )
    (net (code "60") (name "Net-(LED-ON-PadA)") (class "Default")
      (node (ref "LED-ON") (pin "A") (pinfunction "A_A") (pintype "passive"))
      (node (ref "R2") (pin "1") (pinfunction "1_1") (pintype "passive"))
    )
    (net (code "61") (name "Net-(LED-RSSI-PadA)") (class "Default")
      (node (ref "LED-RSSI") (pin "A") (pinfunction "A_A") (pintype "passive"))
      (node (ref "R1") (pin "1") (pinfunction "1_1") (pintype "passive"))
    )
    (net (code "62") (name "Net-(LED1-PadA)") (class "Default")
      (node (ref "LED1") (pin "A") (pinfunction "A_A") (pintype "passive"))
      (node (ref "R11") (pin "2") (pinfunction "2_2") (pintype "passive"))
    )
    (net (code "63") (name "Net-(LED2-PadA)") (class "Default")
      (node (ref "LED2") (pin "A") (pinfunction "A_A") (pintype "passive"))
      (node (ref "R12") (pin "2") (pinfunction "2_2") (pintype "passive"))
    )
    (net (code "64") (name "Net-(Q1-D)") (class "Default")
      (node (ref "JK1") (pin "TIP") (pinfunction "TIP_TIP") (pintype "bidirectional"))
      (node (ref "Q1") (pin "3") (pinfunction "D_3") (pintype "passive"))
      (node (ref "Q2") (pin "3") (pinfunction "D_3") (pintype "passive"))
    )
    (net (code "65") (name "Net-(Q1-S)") (class "Default")
      (node (ref "D2") (pin "C") (pinfunction "C_C") (pintype "passive"))
      (node (ref "Q1") (pin "2") (pinfunction "S_2") (pintype "passive"))
    )
    (net (code "66") (name "Net-(Q2-S)") (class "Default")
      (node (ref "D3") (pin "C") (pinfunction "C_C") (pintype "passive"))
      (node (ref "Q2") (pin "2") (pinfunction "S_2") (pintype "passive"))
    )
    (net (code "67") (name "Net-(Q3-D)") (class "Default")
      (node (ref "JK2") (pin "TIP") (pinfunction "TIP_TIP") (pintype "bidirectional"))
      (node (ref "Q3") (pin "3") (pinfunction "D_3") (pintype "passive"))
      (node (ref "Q4") (pin "3") (pinfunction "D_3") (pintype "passive"))
    )
    (net (code "68") (name "Net-(Q3-S)") (class "Default")
      (node (ref "D4") (pin "C") (pinfunction "C_C") (pintype "passive"))
      (node (ref "Q3") (pin "2") (pinfunction "S_2") (pintype "passive"))
    )
    (net (code "69") (name "Net-(Q4-S)") (class "Default")
      (node (ref "D5") (pin "C") (pinfunction "C_C") (pintype "passive"))
      (node (ref "Q4") (pin "2") (pinfunction "S_2") (pintype "passive"))
    )
    (net (code "70") (name "Net-(Q5-D)") (class "Default")
      (node (ref "JK3") (pin "TIP") (pinfunction "TIP_TIP") (pintype "bidirectional"))
      (node (ref "Q5") (pin "3") (pinfunction "D_3") (pintype "passive"))
      (node (ref "Q6") (pin "3") (pinfunction "D_3") (pintype "passive"))
    )
    (net (code "71") (name "Net-(Q5-S)") (class "Default")
      (node (ref "D6") (pin "C") (pinfunction "C_C") (pintype "passive"))
      (node (ref "Q5") (pin "2") (pinfunction "S_2") (pintype "passive"))
    )
    (net (code "72") (name "Net-(Q6-S)") (class "Default")
      (node (ref "D7") (pin "C") (pinfunction "C_C") (pintype "passive"))
      (node (ref "Q6") (pin "2") (pinfunction "S_2") (pintype "passive"))
    )
    (net (code "73") (name "Net-(Q7-D)") (class "Default")
      (node (ref "JK4") (pin "TIP") (pinfunction "TIP_TIP") (pintype "bidirectional"))
      (node (ref "Q7") (pin "3") (pinfunction "D_3") (pintype "passive"))
      (node (ref "Q8") (pin "3") (pinfunction "D_3") (pintype "passive"))
    )
    (net (code "74") (name "Net-(Q7-S)") (class "Default")
      (node (ref "D8") (pin "C") (pinfunction "C_C") (pintype "passive"))
      (node (ref "Q7") (pin "2") (pinfunction "S_2") (pintype "passive"))
    )
    (net (code "75") (name "Net-(Q8-S)") (class "Default")
      (node (ref "D9") (pin "C") (pinfunction "C_C") (pintype "passive"))
      (node (ref "Q8") (pin "2") (pinfunction "S_2") (pintype "passive"))
    )
    (net (code "76") (name "Net-(U$1-DIO5)") (class "Default")
      (node (ref "R2") (pin "2") (pinfunction "2_2") (pintype "passive"))
      (node (ref "U$1") (pin "15") (pinfunction "DIO5_15") (pintype "bidirectional"))
    )
    (net (code "77") (name "unconnected-(CN1-PadID)") (class "Default")
      (node (ref "CN1") (pin "ID") (pinfunction "ID_ID") (pintype "bidirectional"))
    )
    (net (code "78") (name "unconnected-(D1-PadA)") (class "Default")
      (node (ref "D1") (pin "A") (pinfunction "A_A") (pintype "passive"))
    )
    (net (code "79") (name "unconnected-(IC6-GPB4-Pad5)") (class "Default")
      (node (ref "IC6") (pin "5") (pinfunction "GPB4_5") (pintype "bidirectional"))
    )
    (net (code "80") (name "unconnected-(IC6-GPB5-Pad6)") (class "Default")
      (node (ref "IC6") (pin "6") (pinfunction "GPB5_6") (pintype "bidirectional"))
    )
    (net (code "81") (name "unconnected-(IC6-GPB6-Pad7)") (class "Default")
      (node (ref "IC6") (pin "7") (pinfunction "GPB6_7") (pintype "bidirectional"))
    )
    (net (code "82") (name "unconnected-(IC6-GPB7-Pad8)") (class "Default")
      (node (ref "IC6") (pin "8") (pinfunction "GPB7_8") (pintype "bidirectional"))
    )
    (net (code "83") (name "unconnected-(IC6-INTA-Pad20)") (class "Default")
      (node (ref "IC6") (pin "20") (pinfunction "INTA_20") (pintype "output"))
    )
    (net (code "84") (name "unconnected-(IC6-INTB-Pad19)") (class "Default")
      (node (ref "IC6") (pin "19") (pinfunction "INTB_19") (pintype "output"))
    )
    (net (code "85") (name "unconnected-(IC8-PB4(ADC11)-Pad28)") (class "Default")
      (node (ref "IC8") (pin "28") (pinfunction "PB4(ADC11)_28") (pintype "bidirectional"))
    )
    (net (code "86") (name "unconnected-(IC8-PB5(OC1A{slash}ADC12{slash}~{OC4B})-Pad29)") (class "Default")
      (node (ref "IC8") (pin "29") (pinfunction "PB5(OC1A/ADC12/~{OC4B})_29") (pintype "bidirectional"))
    )
    (net (code "87") (name "unconnected-(IC8-PB6(OC1B{slash}OC4B{slash}ADC13)-Pad30)") (class "Default")
      (node (ref "IC8") (pin "30") (pinfunction "PB6(OC1B/OC4B/ADC13)_30") (pintype "bidirectional"))
    )
    (net (code "88") (name "unconnected-(IC8-PB7(OC0A{slash}OC1C{slash}RTS)-Pad12)") (class "Default")
      (node (ref "IC8") (pin "12") (pinfunction "PB7(OC0A/OC1C/RTS)_12") (pintype "bidirectional"))
    )
    (net (code "89") (name "unconnected-(IC8-PC6(OC3A{slash}~{OC4A})-Pad31)") (class "Default")
      (node (ref "IC8") (pin "31") (pinfunction "PC6(OC3A/~{OC4A})_31") (pintype "bidirectional"))
    )
    (net (code "90") (name "unconnected-(IC8-PC7(ICP3{slash}CLK0{slash}OC4A)-Pad32)") (class "Default")
      (node (ref "IC8") (pin "32") (pinfunction "PC7(ICP3/CLK0/OC4A)_32") (pintype "bidirectional"))
    )
    (net (code "91") (name "unconnected-(IC8-PD4(ICP1{slash}ADC8)-Pad25)") (class "Default")
      (node (ref "IC8") (pin "25") (pinfunction "PD4(ICP1/ADC8)_25") (pintype "bidirectional"))
    )
    (net (code "92") (name "unconnected-(IC8-PD6(T1{slash}ADC9{slash}~{OC4D})-Pad26)") (class "Default")
      (node (ref "IC8") (pin "26") (pinfunction "PD6(T1/ADC9/~{OC4D})_26") (pintype "bidirectional"))
    )
    (net (code "93") (name "unconnected-(IC8-PD7(OC4D{slash}ADC10{slash}T0)-Pad27)") (class "Default")
      (node (ref "IC8") (pin "27") (pinfunction "PD7(OC4D/ADC10/T0)_27") (pintype "bidirectional"))
    )
    (net (code "94") (name "unconnected-(IC8-PE6(INT.6{slash}AIN0)-Pad1)") (class "Default")
      (node (ref "IC8") (pin "1") (pinfunction "PE6(INT.6/AIN0)_1") (pintype "bidirectional"))
    )
    (net (code "95") (name "unconnected-(IC8-PF0(ADC0)-Pad41)") (class "Default")
      (node (ref "IC8") (pin "41") (pinfunction "PF0(ADC0)_41") (pintype "bidirectional"))
    )
    (net (code "96") (name "unconnected-(IC8-PF1(ADC1)-Pad40)") (class "Default")
      (node (ref "IC8") (pin "40") (pinfunction "PF1(ADC1)_40") (pintype "bidirectional"))
    )
    (net (code "97") (name "unconnected-(IC8-PF4(ADC4{slash}TCK)-Pad39)") (class "Default")
      (node (ref "IC8") (pin "39") (pinfunction "PF4(ADC4/TCK)_39") (pintype "bidirectional"))
    )
    (net (code "98") (name "unconnected-(IC8-PF5(ADC5{slash}TMS)-Pad38)") (class "Default")
      (node (ref "IC8") (pin "38") (pinfunction "PF5(ADC5/TMS)_38") (pintype "bidirectional"))
    )
    (net (code "99") (name "unconnected-(IC8-PF6(ADC6{slash}TDO)-Pad37)") (class "Default")
      (node (ref "IC8") (pin "37") (pinfunction "PF6(ADC6/TDO)_37") (pintype "bidirectional"))
    )
    (net (code "100") (name "unconnected-(IC8-PF7(ADC7(TDI)-Pad36)") (class "Default")
      (node (ref "IC8") (pin "36") (pinfunction "PF7(ADC7(TDI)_36") (pintype "bidirectional"))
    )
    (net (code "101") (name "unconnected-(JK1-PadRSH)") (class "Default")
      (node (ref "JK1") (pin "RSH") (pinfunction "RSH_RSH") (pintype "bidirectional"))
    )
    (net (code "102") (name "unconnected-(JK2-PadRSH)") (class "Default")
      (node (ref "JK2") (pin "RSH") (pinfunction "RSH_RSH") (pintype "bidirectional"))
    )
    (net (code "103") (name "unconnected-(JK3-PadRSH)") (class "Default")
      (node (ref "JK3") (pin "RSH") (pinfunction "RSH_RSH") (pintype "bidirectional"))
    )
    (net (code "104") (name "unconnected-(JK4-PadRSH)") (class "Default")
      (node (ref "JK4") (pin "RSH") (pinfunction "RSH_RSH") (pintype "bidirectional"))
    )
    (net (code "105") (name "unconnected-(U$1-DIO0-Pad20)") (class "Default")
      (node (ref "U$1") (pin "20") (pinfunction "DIO0_20") (pintype "bidirectional"))
    )
    (net (code "106") (name "unconnected-(U$1-DIO1-Pad19)") (class "Default")
      (node (ref "U$1") (pin "19") (pinfunction "DIO1_19") (pintype "bidirectional"))
    )
    (net (code "107") (name "unconnected-(U$1-DIO2-Pad18)") (class "Default")
      (node (ref "U$1") (pin "18") (pinfunction "DIO2_18") (pintype "bidirectional"))
    )
    (net (code "108") (name "unconnected-(U$1-DIO3-Pad17)") (class "Default")
      (node (ref "U$1") (pin "17") (pinfunction "DIO3_17") (pintype "bidirectional"))
    )
    (net (code "109") (name "unconnected-(U$1-DIO4-Pad11)") (class "Default")
      (node (ref "U$1") (pin "11") (pinfunction "DIO4_11") (pintype "bidirectional"))
    )
    (net (code "110") (name "unconnected-(U$1-DIO9-Pad13)") (class "Default")
      (node (ref "U$1") (pin "13") (pinfunction "DIO9_13") (pintype "bidirectional"))
    )
    (net (code "111") (name "unconnected-(U$1-DIO11-Pad7)") (class "Default")
      (node (ref "U$1") (pin "7") (pinfunction "DIO11_7") (pintype "bidirectional"))
    )
    (net (code "112") (name "unconnected-(U$1-DIO12-Pad4)") (class "Default")
      (node (ref "U$1") (pin "4") (pinfunction "DIO12_4") (pintype "bidirectional"))
    )
    (net (code "113") (name "unconnected-(U$1-RES-Pad8)") (class "Default")
      (node (ref "U$1") (pin "8") (pinfunction "RES_8") (pintype "bidirectional"))
    )
    (net (code "114") (name "unconnected-(U$1-RES-Pad14)") (class "Default")
      (node (ref "U$1") (pin "14") (pinfunction "RES_14") (pintype "bidirectional"))
    )
  )
)
